# IO1.net
KiCad netlist of a schematic drawn in Altium Designer
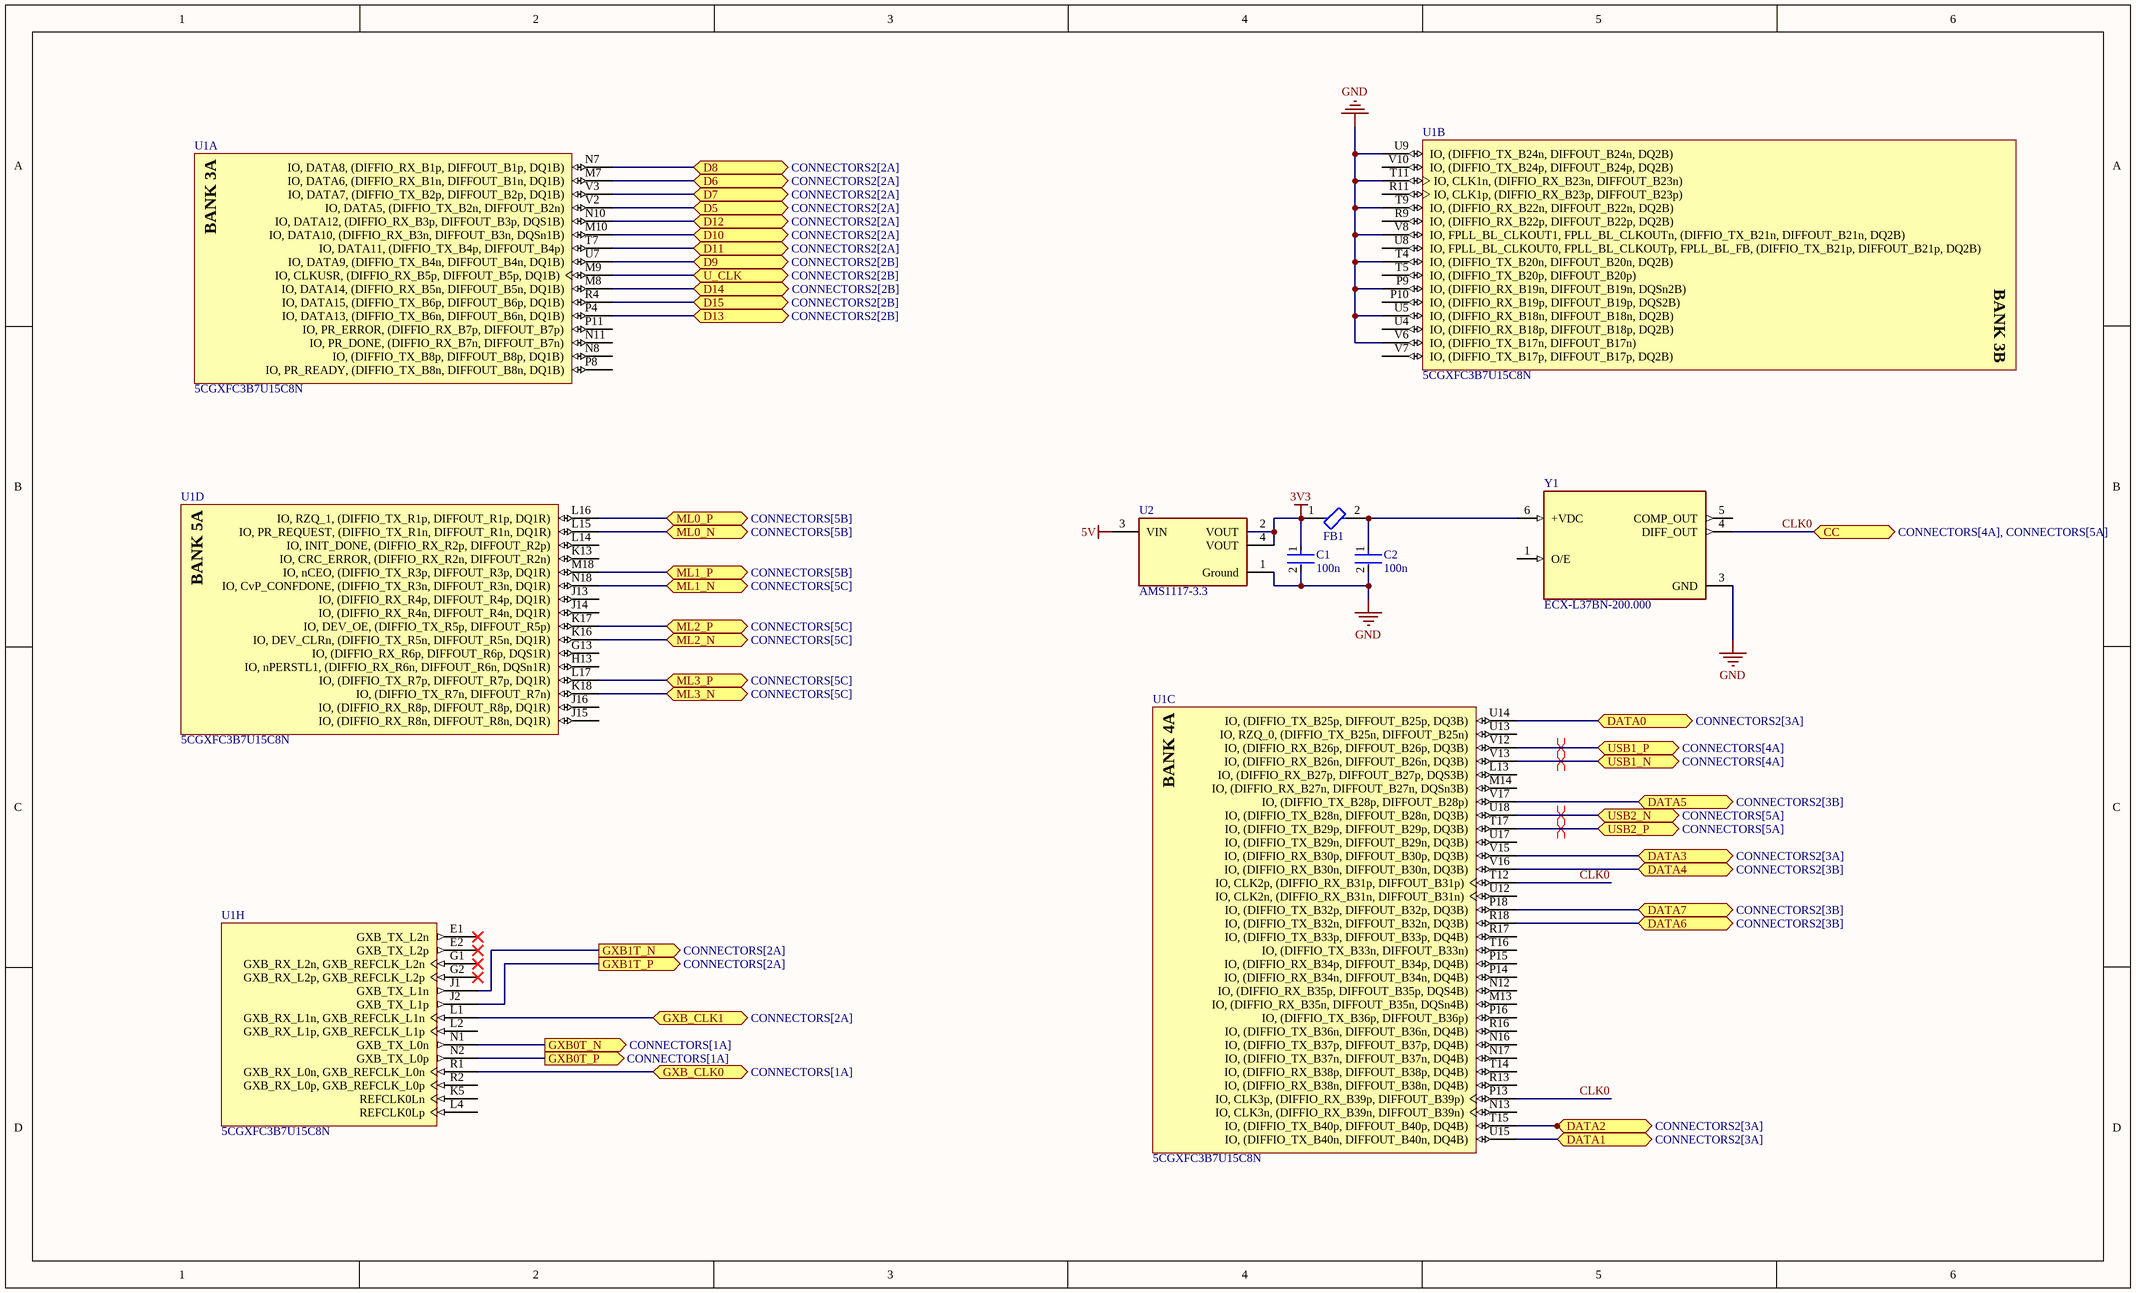
[diagram p0: IO1.SchDoc]

(export (version "E")
  (design (tool "Eeschema 10.0.6"))
  (components
    (comp (ref "C1")
      (value "100n")
      (footprint "FP-CL10-IPC_C")
      (description "Cap Ceramic 4.7uF 10V X5R ±10% Pad SMD 0603 +85°C T/R")
      (fields (field (name "TOLERANCE") "10%"))
      (libsource (lib "Altium Content Vault") (part "b4654b650e69147ec39a6b967a45e02"))
    )
    (comp (ref "C2")
      (value "100n")
      (footprint "FP-CL10-IPC_C")
      (description "Cap Ceramic 4.7uF 10V X5R ±10% Pad SMD 0603 +85°C T/R")
      (fields (field (name "TOLERANCE") "10%"))
      (libsource (lib "Altium Content Vault") (part "b4654b650e69147ec39a6b967a45e02"))
    )
    (comp (ref "FB1")
      (value "BLM18KG121TN1D")
      (footprint "FP-BLM18-0_15-t0_6-d1_2-IPC_A")
      (description "FERRITE BEAD 120 OHM 0603 1LN")
      (fields (field (name "TOLERANCE") "25%"))
      (libsource (lib "Altium Content Vault") (part "5f30dd21d616792df468990f7003faa"))
    )
    (comp (ref "U1")
      (value "5CGXFC3B7U15C8N")
      (footprint "ALTR-UBGA324_A-150")
      (fields (field (name "MANUFACTURER") "Altera"))
      (libsource (lib "") (part "ALTR-5CGXFC3B6U15_1"))
    )
    (comp (ref "U2")
      (value "AMS1117-3.3")
      (footprint "FP-AMS1117-IPC_C")
      (description "LDO Voltage Regulators 1A, 3.3V")
      (fields
        (field (name "OCTOPART") "https://octopart.com/ams1117-3.3-advanced+monolithic+systems-25899300")
        (field (name "MANUFACTURER") "Advanced Monolithic Systems")
      )
      (libsource (lib "Altium Content Vault") (part "8bdbb5f8e77002000e30dd2845d0354"))
    )
    (comp (ref "Y1")
      (value "ECX-L37BN-200.000")
      (footprint "OSC_ECX-L37BN-200.000")
      (description "200 MHz XO (Standard) LVDS Oscillator 3.3V Enable/Disable 6-SMD, No Lead")
      (fields (field (name "MF") "ECS Inc."))
      (libsource (lib "ECX-L37BN-200.000") (part "ECX-L37BN-200.000"))
    )
  )
  (nets
    (net (code "1") (name "/CLK0") (class "Default")
      (node (ref "U1") (pin "P13") (pinfunction "IO,_CLK3p,_(DIFFIO_RX_B39p,_DIFFOUT_B39p)_P13") (pintype "bidirectional"))
      (node (ref "U1") (pin "T12") (pinfunction "IO,_CLK2p,_(DIFFIO_RX_B31p,_DIFFOUT_B31p)_T12") (pintype "bidirectional"))
      (node (ref "Y1") (pin "4") (pinfunction "DIFF_OUT_4") (pintype "output"))
    )
    (net (code "2") (name "/D5") (class "Default")
      (node (ref "U1") (pin "V2") (pinfunction "IO,_DATA5,_(DIFFIO_TX_B2n,_DIFFOUT_B2n)_V2") (pintype "bidirectional"))
    )
    (net (code "3") (name "/D6") (class "Default")
      (node (ref "U1") (pin "M7") (pinfunction "IO,_DATA6,_(DIFFIO_RX_B1n,_DIFFOUT_B1n,_DQ1B)_M7") (pintype "bidirectional"))
    )
    (net (code "4") (name "/D7") (class "Default")
      (node (ref "U1") (pin "V3") (pinfunction "IO,_DATA7,_(DIFFIO_TX_B2p,_DIFFOUT_B2p,_DQ1B)_V3") (pintype "bidirectional"))
    )
    (net (code "5") (name "/D8") (class "Default")
      (node (ref "U1") (pin "N7") (pinfunction "IO,_DATA8,_(DIFFIO_RX_B1p,_DIFFOUT_B1p,_DQ1B)_N7") (pintype "bidirectional"))
    )
    (net (code "6") (name "/D9") (class "Default")
      (node (ref "U1") (pin "U7") (pinfunction "IO,_DATA9,_(DIFFIO_TX_B4n,_DIFFOUT_B4n,_DQ1B)_U7") (pintype "bidirectional"))
    )
    (net (code "7") (name "/D10") (class "Default")
      (node (ref "U1") (pin "M10") (pinfunction "IO,_DATA10,_(DIFFIO_RX_B3n,_DIFFOUT_B3n,_DQSn1B)_M10") (pintype "bidirectional"))
    )
    (net (code "8") (name "/D11") (class "Default")
      (node (ref "U1") (pin "T7") (pinfunction "IO,_DATA11,_(DIFFIO_TX_B4p,_DIFFOUT_B4p)_T7") (pintype "bidirectional"))
    )
    (net (code "9") (name "/D12") (class "Default")
      (node (ref "U1") (pin "N10") (pinfunction "IO,_DATA12,_(DIFFIO_RX_B3p,_DIFFOUT_B3p,_DQS1B)_N10") (pintype "bidirectional"))
    )
    (net (code "10") (name "/D13") (class "Default")
      (node (ref "U1") (pin "P4") (pinfunction "IO,_DATA13,_(DIFFIO_TX_B6n,_DIFFOUT_B6n,_DQ1B)_P4") (pintype "bidirectional"))
    )
    (net (code "11") (name "/D14") (class "Default")
      (node (ref "U1") (pin "M8") (pinfunction "IO,_DATA14,_(DIFFIO_RX_B5n,_DIFFOUT_B5n,_DQ1B)_M8") (pintype "bidirectional"))
    )
    (net (code "12") (name "/D15") (class "Default")
      (node (ref "U1") (pin "R4") (pinfunction "IO,_DATA15,_(DIFFIO_TX_B6p,_DIFFOUT_B6p,_DQ1B)_R4") (pintype "bidirectional"))
    )
    (net (code "13") (name "/DATA0") (class "Default")
      (node (ref "U1") (pin "U14") (pinfunction "IO,_(DIFFIO_TX_B25p,_DIFFOUT_B25p,_DQ3B)_U14") (pintype "bidirectional"))
    )
    (net (code "14") (name "/DATA1") (class "Default")
      (node (ref "U1") (pin "U15") (pinfunction "IO,_(DIFFIO_TX_B40n,_DIFFOUT_B40n,_DQ4B)_U15") (pintype "bidirectional"))
    )
    (net (code "15") (name "/DATA2") (class "Default")
      (node (ref "U1") (pin "T15") (pinfunction "IO,_(DIFFIO_TX_B40p,_DIFFOUT_B40p,_DQ4B)_T15") (pintype "bidirectional"))
    )
    (net (code "16") (name "/DATA3") (class "Default")
      (node (ref "U1") (pin "V15") (pinfunction "IO,_(DIFFIO_RX_B30p,_DIFFOUT_B30p,_DQ3B)_V15") (pintype "bidirectional"))
    )
    (net (code "17") (name "/DATA4") (class "Default")
      (node (ref "U1") (pin "V16") (pinfunction "IO,_(DIFFIO_RX_B30n,_DIFFOUT_B30n,_DQ3B)_V16") (pintype "bidirectional"))
    )
    (net (code "18") (name "/DATA5") (class "Default")
      (node (ref "U1") (pin "V17") (pinfunction "IO,_(DIFFIO_TX_B28p,_DIFFOUT_B28p)_V17") (pintype "bidirectional"))
    )
    (net (code "19") (name "/DATA6") (class "Default")
      (node (ref "U1") (pin "R18") (pinfunction "IO,_(DIFFIO_TX_B32n,_DIFFOUT_B32n,_DQ3B)_R18") (pintype "bidirectional"))
    )
    (net (code "20") (name "/DATA7") (class "Default")
      (node (ref "U1") (pin "P18") (pinfunction "IO,_(DIFFIO_TX_B32p,_DIFFOUT_B32p,_DQ3B)_P18") (pintype "bidirectional"))
    )
    (net (code "21") (name "/GXB0T_N") (class "Default")
      (node (ref "U1") (pin "N1") (pinfunction "GXB_TX_L0n_N1") (pintype "output"))
    )
    (net (code "22") (name "/GXB0T_P") (class "Default")
      (node (ref "U1") (pin "N2") (pinfunction "GXB_TX_L0p_N2") (pintype "output"))
    )
    (net (code "23") (name "/GXB1T_N") (class "Default")
      (node (ref "U1") (pin "J1") (pinfunction "GXB_TX_L1n_J1") (pintype "output"))
    )
    (net (code "24") (name "/GXB1T_P") (class "Default")
      (node (ref "U1") (pin "J2") (pinfunction "GXB_TX_L1p_J2") (pintype "output"))
    )
    (net (code "25") (name "/GXB_CLK0") (class "Default")
      (node (ref "U1") (pin "R1") (pinfunction "GXB_RX_L0n,_GXB_REFCLK_L0n_R1") (pintype "input"))
    )
    (net (code "26") (name "/GXB_CLK1") (class "Default")
      (node (ref "U1") (pin "L1") (pinfunction "GXB_RX_L1n,_GXB_REFCLK_L1n_L1") (pintype "input"))
    )
    (net (code "27") (name "/ML0_N") (class "Default")
      (node (ref "U1") (pin "L15") (pinfunction "IO,_PR_REQUEST,_(DIFFIO_TX_R1n,_DIFFOUT_R1n,_DQ1R)_L15") (pintype "bidirectional"))
    )
    (net (code "28") (name "/ML0_P") (class "Default")
      (node (ref "U1") (pin "L16") (pinfunction "IO,_RZQ_1,_(DIFFIO_TX_R1p,_DIFFOUT_R1p,_DQ1R)_L16") (pintype "bidirectional"))
    )
    (net (code "29") (name "/ML1_N") (class "Default")
      (node (ref "U1") (pin "N18") (pinfunction "IO,_CvP_CONFDONE,_(DIFFIO_TX_R3n,_DIFFOUT_R3n,_DQ1R)_N18") (pintype "bidirectional"))
    )
    (net (code "30") (name "/ML1_P") (class "Default")
      (node (ref "U1") (pin "M18") (pinfunction "IO,_nCEO,_(DIFFIO_TX_R3p,_DIFFOUT_R3p,_DQ1R)_M18") (pintype "bidirectional"))
    )
    (net (code "31") (name "/ML2_N") (class "Default")
      (node (ref "U1") (pin "K16") (pinfunction "IO,_DEV_CLRn,_(DIFFIO_TX_R5n,_DIFFOUT_R5n,_DQ1R)_K16") (pintype "bidirectional"))
    )
    (net (code "32") (name "/ML2_P") (class "Default")
      (node (ref "U1") (pin "K17") (pinfunction "IO,_DEV_OE,_(DIFFIO_TX_R5p,_DIFFOUT_R5p)_K17") (pintype "bidirectional"))
    )
    (net (code "33") (name "/ML3_N") (class "Default")
      (node (ref "U1") (pin "K18") (pinfunction "IO,_(DIFFIO_TX_R7n,_DIFFOUT_R7n)_K18") (pintype "bidirectional"))
    )
    (net (code "34") (name "/ML3_P") (class "Default")
      (node (ref "U1") (pin "L17") (pinfunction "IO,_(DIFFIO_TX_R7p,_DIFFOUT_R7p,_DQ1R)_L17") (pintype "bidirectional"))
    )
    (net (code "35") (name "/USB1_N") (class "Default")
      (node (ref "U1") (pin "V13") (pinfunction "IO,_(DIFFIO_RX_B26n,_DIFFOUT_B26n,_DQ3B)_V13") (pintype "bidirectional"))
    )
    (net (code "36") (name "/USB1_P") (class "Default")
      (node (ref "U1") (pin "V12") (pinfunction "IO,_(DIFFIO_RX_B26p,_DIFFOUT_B26p,_DQ3B)_V12") (pintype "bidirectional"))
    )
    (net (code "37") (name "/USB2_N") (class "Default")
      (node (ref "U1") (pin "U18") (pinfunction "IO,_(DIFFIO_TX_B28n,_DIFFOUT_B28n,_DQ3B)_U18") (pintype "bidirectional"))
    )
    (net (code "38") (name "/USB2_P") (class "Default")
      (node (ref "U1") (pin "T17") (pinfunction "IO,_(DIFFIO_TX_B29p,_DIFFOUT_B29p,_DQ3B)_T17") (pintype "bidirectional"))
    )
    (net (code "39") (name "/U_CLK") (class "Default")
      (node (ref "U1") (pin "M9") (pinfunction "IO,_CLKUSR,_(DIFFIO_RX_B5p,_DIFFOUT_B5p,_DQ1B)_M9") (pintype "bidirectional"))
    )
    (net (code "40") (name "3V3") (class "Default")
      (node (ref "C1") (pin "1") (pinfunction "1_1") (pintype "passive"))
      (node (ref "FB1") (pin "1") (pinfunction "1_1") (pintype "passive"))
      (node (ref "U2") (pin "2") (pinfunction "VOUT_2") (pintype "passive"))
      (node (ref "U2") (pin "4") (pinfunction "VOUT_4") (pintype "passive"))
    )
    (net (code "41") (name "5V") (class "Default")
      (node (ref "U2") (pin "3") (pinfunction "VIN_3") (pintype "power_in"))
    )
    (net (code "42") (name "GND") (class "Default")
      (node (ref "C1") (pin "2") (pinfunction "2_2") (pintype "passive"))
      (node (ref "C2") (pin "2") (pinfunction "2_2") (pintype "passive"))
      (node (ref "U1") (pin "P9") (pinfunction "IO,_(DIFFIO_RX_B19n,_DIFFOUT_B19n,_DQSn2B)_P9") (pintype "bidirectional"))
      (node (ref "U1") (pin "T11") (pinfunction "IO,_CLK1n,_(DIFFIO_RX_B23n,_DIFFOUT_B23n)_T11") (pintype "bidirectional"))
      (node (ref "U1") (pin "T4") (pinfunction "IO,_(DIFFIO_TX_B20n,_DIFFOUT_B20n,_DQ2B)_T4") (pintype "bidirectional"))
      (node (ref "U1") (pin "T9") (pinfunction "IO,_(DIFFIO_RX_B22n,_DIFFOUT_B22n,_DQ2B)_T9") (pintype "bidirectional"))
      (node (ref "U1") (pin "U5") (pinfunction "IO,_(DIFFIO_RX_B18n,_DIFFOUT_B18n,_DQ2B)_U5") (pintype "bidirectional"))
      (node (ref "U1") (pin "U9") (pinfunction "IO,_(DIFFIO_TX_B24n,_DIFFOUT_B24n,_DQ2B)_U9") (pintype "bidirectional"))
      (node (ref "U1") (pin "V6") (pinfunction "IO,_(DIFFIO_TX_B17n,_DIFFOUT_B17n)_V6") (pintype "bidirectional"))
      (node (ref "U1") (pin "V8") (pinfunction "IO,_FPLL_BL_CLKOUT1,_FPLL_BL_CLKOUTn,_(DIFFIO_TX_B21n,_DIFFOUT_B21n,_DQ2B)_V8") (pintype "bidirectional"))
      (node (ref "U2") (pin "1") (pinfunction "Ground_1") (pintype "power_in"))
      (node (ref "Y1") (pin "3") (pinfunction "GND_3") (pintype "power_in"))
    )
    (net (code "43") (name "Net-(Y1-+VDC)") (class "Default")
      (node (ref "C2") (pin "1") (pinfunction "1_1") (pintype "passive"))
      (node (ref "FB1") (pin "2") (pinfunction "2_2") (pintype "passive"))
      (node (ref "Y1") (pin "6") (pinfunction "+VDC_6") (pintype "input"))
    )
    (net (code "44") (name "unconnected-(U1A-IO,_(DIFFIO_TX_B8p,_DIFFOUT_B8p,_DQ1B)-PadN8)") (class "Default")
      (node (ref "U1") (pin "N8") (pinfunction "IO,_(DIFFIO_TX_B8p,_DIFFOUT_B8p,_DQ1B)_N8") (pintype "bidirectional"))
    )
    (net (code "45") (name "unconnected-(U1A-IO,_PR_DONE,_(DIFFIO_RX_B7n,_DIFFOUT_B7n)-PadN11)") (class "Default")
      (node (ref "U1") (pin "N11") (pinfunction "IO,_PR_DONE,_(DIFFIO_RX_B7n,_DIFFOUT_B7n)_N11") (pintype "bidirectional"))
    )
    (net (code "46") (name "unconnected-(U1A-IO,_PR_ERROR,_(DIFFIO_RX_B7p,_DIFFOUT_B7p)-PadP11)") (class "Default")
      (node (ref "U1") (pin "P11") (pinfunction "IO,_PR_ERROR,_(DIFFIO_RX_B7p,_DIFFOUT_B7p)_P11") (pintype "bidirectional"))
    )
    (net (code "47") (name "unconnected-(U1A-IO,_PR_READY,_(DIFFIO_TX_B8n,_DIFFOUT_B8n,_DQ1B)-PadP8)") (class "Default")
      (node (ref "U1") (pin "P8") (pinfunction "IO,_PR_READY,_(DIFFIO_TX_B8n,_DIFFOUT_B8n,_DQ1B)_P8") (pintype "bidirectional"))
    )
    (net (code "48") (name "unconnected-(U1B-IO,_(DIFFIO_RX_B18p,_DIFFOUT_B18p,_DQ2B)-PadU4)") (class "Default")
      (node (ref "U1") (pin "U4") (pinfunction "IO,_(DIFFIO_RX_B18p,_DIFFOUT_B18p,_DQ2B)_U4") (pintype "bidirectional"))
    )
    (net (code "49") (name "unconnected-(U1B-IO,_(DIFFIO_RX_B19p,_DIFFOUT_B19p,_DQS2B)-PadP10)") (class "Default")
      (node (ref "U1") (pin "P10") (pinfunction "IO,_(DIFFIO_RX_B19p,_DIFFOUT_B19p,_DQS2B)_P10") (pintype "bidirectional"))
    )
    (net (code "50") (name "unconnected-(U1B-IO,_(DIFFIO_RX_B22p,_DIFFOUT_B22p,_DQ2B)-PadR9)") (class "Default")
      (node (ref "U1") (pin "R9") (pinfunction "IO,_(DIFFIO_RX_B22p,_DIFFOUT_B22p,_DQ2B)_R9") (pintype "bidirectional"))
    )
    (net (code "51") (name "unconnected-(U1B-IO,_(DIFFIO_TX_B17p,_DIFFOUT_B17p,_DQ2B)-PadV7)") (class "Default")
      (node (ref "U1") (pin "V7") (pinfunction "IO,_(DIFFIO_TX_B17p,_DIFFOUT_B17p,_DQ2B)_V7") (pintype "bidirectional"))
    )
    (net (code "52") (name "unconnected-(U1B-IO,_(DIFFIO_TX_B20p,_DIFFOUT_B20p)-PadT5)") (class "Default")
      (node (ref "U1") (pin "T5") (pinfunction "IO,_(DIFFIO_TX_B20p,_DIFFOUT_B20p)_T5") (pintype "bidirectional"))
    )
    (net (code "53") (name "unconnected-(U1B-IO,_(DIFFIO_TX_B24p,_DIFFOUT_B24p,_DQ2B)-PadV10)") (class "Default")
      (node (ref "U1") (pin "V10") (pinfunction "IO,_(DIFFIO_TX_B24p,_DIFFOUT_B24p,_DQ2B)_V10") (pintype "bidirectional"))
    )
    (net (code "54") (name "unconnected-(U1B-IO,_CLK1p,_(DIFFIO_RX_B23p,_DIFFOUT_B23p)-PadR11)") (class "Default")
      (node (ref "U1") (pin "R11") (pinfunction "IO,_CLK1p,_(DIFFIO_RX_B23p,_DIFFOUT_B23p)_R11") (pintype "bidirectional"))
    )
    (net (code "55") (name "unconnected-(U1B-IO,_FPLL_BL_CLKOUT0,_FPLL_BL_CLKOUTp,_FPLL_BL_FB,_(DIFFIO_TX_B21p,_DIFFOUT_B21p,_DQ2B)-PadU8)") (class "Default")
      (node (ref "U1") (pin "U8") (pinfunction "IO,_FPLL_BL_CLKOUT0,_FPLL_BL_CLKOUTp,_FPLL_BL_FB,_(DIFFIO_TX_B21p,_DIFFOUT_B21p,_DQ2B)_U8") (pintype "bidirectional"))
    )
    (net (code "56") (name "unconnected-(U1C-IO,_(DIFFIO_RX_B27n,_DIFFOUT_B27n,_DQSn3B)-PadM14)") (class "Default")
      (node (ref "U1") (pin "M14") (pinfunction "IO,_(DIFFIO_RX_B27n,_DIFFOUT_B27n,_DQSn3B)_M14") (pintype "bidirectional"))
    )
    (net (code "57") (name "unconnected-(U1C-IO,_(DIFFIO_RX_B27p,_DIFFOUT_B27p,_DQS3B)-PadL13)") (class "Default")
      (node (ref "U1") (pin "L13") (pinfunction "IO,_(DIFFIO_RX_B27p,_DIFFOUT_B27p,_DQS3B)_L13") (pintype "bidirectional"))
    )
    (net (code "58") (name "unconnected-(U1C-IO,_(DIFFIO_RX_B34n,_DIFFOUT_B34n,_DQ4B)-PadP14)") (class "Default")
      (node (ref "U1") (pin "P14") (pinfunction "IO,_(DIFFIO_RX_B34n,_DIFFOUT_B34n,_DQ4B)_P14") (pintype "bidirectional"))
    )
    (net (code "59") (name "unconnected-(U1C-IO,_(DIFFIO_RX_B34p,_DIFFOUT_B34p,_DQ4B)-PadP15)") (class "Default")
      (node (ref "U1") (pin "P15") (pinfunction "IO,_(DIFFIO_RX_B34p,_DIFFOUT_B34p,_DQ4B)_P15") (pintype "bidirectional"))
    )
    (net (code "60") (name "unconnected-(U1C-IO,_(DIFFIO_RX_B35n,_DIFFOUT_B35n,_DQSn4B)-PadM13)") (class "Default")
      (node (ref "U1") (pin "M13") (pinfunction "IO,_(DIFFIO_RX_B35n,_DIFFOUT_B35n,_DQSn4B)_M13") (pintype "bidirectional"))
    )
    (net (code "61") (name "unconnected-(U1C-IO,_(DIFFIO_RX_B35p,_DIFFOUT_B35p,_DQS4B)-PadN12)") (class "Default")
      (node (ref "U1") (pin "N12") (pinfunction "IO,_(DIFFIO_RX_B35p,_DIFFOUT_B35p,_DQS4B)_N12") (pintype "bidirectional"))
    )
    (net (code "62") (name "unconnected-(U1C-IO,_(DIFFIO_RX_B38n,_DIFFOUT_B38n,_DQ4B)-PadR13)") (class "Default")
      (node (ref "U1") (pin "R13") (pinfunction "IO,_(DIFFIO_RX_B38n,_DIFFOUT_B38n,_DQ4B)_R13") (pintype "bidirectional"))
    )
    (net (code "63") (name "unconnected-(U1C-IO,_(DIFFIO_RX_B38p,_DIFFOUT_B38p,_DQ4B)-PadT14)") (class "Default")
      (node (ref "U1") (pin "T14") (pinfunction "IO,_(DIFFIO_RX_B38p,_DIFFOUT_B38p,_DQ4B)_T14") (pintype "bidirectional"))
    )
    (net (code "64") (name "unconnected-(U1C-IO,_(DIFFIO_TX_B29n,_DIFFOUT_B29n,_DQ3B)-PadU17)") (class "Default")
      (node (ref "U1") (pin "U17") (pinfunction "IO,_(DIFFIO_TX_B29n,_DIFFOUT_B29n,_DQ3B)_U17") (pintype "bidirectional"))
    )
    (net (code "65") (name "unconnected-(U1C-IO,_(DIFFIO_TX_B33n,_DIFFOUT_B33n)-PadT16)") (class "Default")
      (node (ref "U1") (pin "T16") (pinfunction "IO,_(DIFFIO_TX_B33n,_DIFFOUT_B33n)_T16") (pintype "bidirectional"))
    )
    (net (code "66") (name "unconnected-(U1C-IO,_(DIFFIO_TX_B33p,_DIFFOUT_B33p,_DQ4B)-PadR17)") (class "Default")
      (node (ref "U1") (pin "R17") (pinfunction "IO,_(DIFFIO_TX_B33p,_DIFFOUT_B33p,_DQ4B)_R17") (pintype "bidirectional"))
    )
    (net (code "67") (name "unconnected-(U1C-IO,_(DIFFIO_TX_B36n,_DIFFOUT_B36n,_DQ4B)-PadR16)") (class "Default")
      (node (ref "U1") (pin "R16") (pinfunction "IO,_(DIFFIO_TX_B36n,_DIFFOUT_B36n,_DQ4B)_R16") (pintype "bidirectional"))
    )
    (net (code "68") (name "unconnected-(U1C-IO,_(DIFFIO_TX_B36p,_DIFFOUT_B36p)-PadP16)") (class "Default")
      (node (ref "U1") (pin "P16") (pinfunction "IO,_(DIFFIO_TX_B36p,_DIFFOUT_B36p)_P16") (pintype "bidirectional"))
    )
    (net (code "69") (name "unconnected-(U1C-IO,_(DIFFIO_TX_B37n,_DIFFOUT_B37n,_DQ4B)-PadN17)") (class "Default")
      (node (ref "U1") (pin "N17") (pinfunction "IO,_(DIFFIO_TX_B37n,_DIFFOUT_B37n,_DQ4B)_N17") (pintype "bidirectional"))
    )
    (net (code "70") (name "unconnected-(U1C-IO,_(DIFFIO_TX_B37p,_DIFFOUT_B37p,_DQ4B)-PadN16)") (class "Default")
      (node (ref "U1") (pin "N16") (pinfunction "IO,_(DIFFIO_TX_B37p,_DIFFOUT_B37p,_DQ4B)_N16") (pintype "bidirectional"))
    )
    (net (code "71") (name "unconnected-(U1C-IO,_CLK2n,_(DIFFIO_RX_B31n,_DIFFOUT_B31n)-PadU12)") (class "Default")
      (node (ref "U1") (pin "U12") (pinfunction "IO,_CLK2n,_(DIFFIO_RX_B31n,_DIFFOUT_B31n)_U12") (pintype "bidirectional"))
    )
    (net (code "72") (name "unconnected-(U1C-IO,_CLK3n,_(DIFFIO_RX_B39n,_DIFFOUT_B39n)-PadN13)") (class "Default")
      (node (ref "U1") (pin "N13") (pinfunction "IO,_CLK3n,_(DIFFIO_RX_B39n,_DIFFOUT_B39n)_N13") (pintype "bidirectional"))
    )
    (net (code "73") (name "unconnected-(U1C-IO,_RZQ_0,_(DIFFIO_TX_B25n,_DIFFOUT_B25n)-PadU13)") (class "Default")
      (node (ref "U1") (pin "U13") (pinfunction "IO,_RZQ_0,_(DIFFIO_TX_B25n,_DIFFOUT_B25n)_U13") (pintype "bidirectional"))
    )
    (net (code "74") (name "unconnected-(U1D-IO,_(DIFFIO_RX_R4n,_DIFFOUT_R4n,_DQ1R)-PadJ14)") (class "Default")
      (node (ref "U1") (pin "J14") (pinfunction "IO,_(DIFFIO_RX_R4n,_DIFFOUT_R4n,_DQ1R)_J14") (pintype "bidirectional"))
    )
    (net (code "75") (name "unconnected-(U1D-IO,_(DIFFIO_RX_R4p,_DIFFOUT_R4p,_DQ1R)-PadJ13)") (class "Default")
      (node (ref "U1") (pin "J13") (pinfunction "IO,_(DIFFIO_RX_R4p,_DIFFOUT_R4p,_DQ1R)_J13") (pintype "bidirectional"))
    )
    (net (code "76") (name "unconnected-(U1D-IO,_(DIFFIO_RX_R6p,_DIFFOUT_R6p,_DQS1R)-PadG13)") (class "Default")
      (node (ref "U1") (pin "G13") (pinfunction "IO,_(DIFFIO_RX_R6p,_DIFFOUT_R6p,_DQS1R)_G13") (pintype "bidirectional"))
    )
    (net (code "77") (name "unconnected-(U1D-IO,_(DIFFIO_RX_R8n,_DIFFOUT_R8n,_DQ1R)-PadJ15)") (class "Default")
      (node (ref "U1") (pin "J15") (pinfunction "IO,_(DIFFIO_RX_R8n,_DIFFOUT_R8n,_DQ1R)_J15") (pintype "bidirectional"))
    )
    (net (code "78") (name "unconnected-(U1D-IO,_(DIFFIO_RX_R8p,_DIFFOUT_R8p,_DQ1R)-PadJ16)") (class "Default")
      (node (ref "U1") (pin "J16") (pinfunction "IO,_(DIFFIO_RX_R8p,_DIFFOUT_R8p,_DQ1R)_J16") (pintype "bidirectional"))
    )
    (net (code "79") (name "unconnected-(U1D-IO,_CRC_ERROR,_(DIFFIO_RX_R2n,_DIFFOUT_R2n)-PadK13)") (class "Default")
      (node (ref "U1") (pin "K13") (pinfunction "IO,_CRC_ERROR,_(DIFFIO_RX_R2n,_DIFFOUT_R2n)_K13") (pintype "bidirectional"))
    )
    (net (code "80") (name "unconnected-(U1D-IO,_INIT_DONE,_(DIFFIO_RX_R2p,_DIFFOUT_R2p)-PadL14)") (class "Default")
      (node (ref "U1") (pin "L14") (pinfunction "IO,_INIT_DONE,_(DIFFIO_RX_R2p,_DIFFOUT_R2p)_L14") (pintype "bidirectional"))
    )
    (net (code "81") (name "unconnected-(U1D-IO,_nPERSTL1,_(DIFFIO_RX_R6n,_DIFFOUT_R6n,_DQSn1R)-PadH13)") (class "Default")
      (node (ref "U1") (pin "H13") (pinfunction "IO,_nPERSTL1,_(DIFFIO_RX_R6n,_DIFFOUT_R6n,_DQSn1R)_H13") (pintype "bidirectional"))
    )
    (net (code "82") (name "unconnected-(U1H-GXB_RX_L0p,_GXB_REFCLK_L0p-PadR2)") (class "Default")
      (node (ref "U1") (pin "R2") (pinfunction "GXB_RX_L0p,_GXB_REFCLK_L0p_R2") (pintype "input"))
    )
    (net (code "83") (name "unconnected-(U1H-GXB_RX_L1p,_GXB_REFCLK_L1p-PadL2)") (class "Default")
      (node (ref "U1") (pin "L2") (pinfunction "GXB_RX_L1p,_GXB_REFCLK_L1p_L2") (pintype "input"))
    )
    (net (code "84") (name "unconnected-(U1H-GXB_RX_L2n,_GXB_REFCLK_L2n-PadG1)") (class "Default")
      (node (ref "U1") (pin "G1") (pinfunction "GXB_RX_L2n,_GXB_REFCLK_L2n_G1") (pintype "input+no_connect"))
    )
    (net (code "85") (name "unconnected-(U1H-GXB_RX_L2p,_GXB_REFCLK_L2p-PadG2)") (class "Default")
      (node (ref "U1") (pin "G2") (pinfunction "GXB_RX_L2p,_GXB_REFCLK_L2p_G2") (pintype "input+no_connect"))
    )
    (net (code "86") (name "unconnected-(U1H-GXB_TX_L2n-PadE1)") (class "Default")
      (node (ref "U1") (pin "E1") (pinfunction "GXB_TX_L2n_E1") (pintype "output+no_connect"))
    )
    (net (code "87") (name "unconnected-(U1H-GXB_TX_L2p-PadE2)") (class "Default")
      (node (ref "U1") (pin "E2") (pinfunction "GXB_TX_L2p_E2") (pintype "output+no_connect"))
    )
    (net (code "88") (name "unconnected-(U1H-REFCLK0Ln-PadK5)") (class "Default")
      (node (ref "U1") (pin "K5") (pinfunction "REFCLK0Ln_K5") (pintype "input"))
    )
    (net (code "89") (name "unconnected-(U1H-REFCLK0Lp-PadL4)") (class "Default")
      (node (ref "U1") (pin "L4") (pinfunction "REFCLK0Lp_L4") (pintype "input"))
    )
    (net (code "90") (name "unconnected-(Y1-COMP_OUT-Pad5)") (class "Default")
      (node (ref "Y1") (pin "5") (pinfunction "COMP_OUT_5") (pintype "output"))
    )
    (net (code "91") (name "unconnected-(Y1-O{slash}E-Pad1)") (class "Default")
      (node (ref "Y1") (pin "1") (pinfunction "O/E_1") (pintype "input"))
    )
  )
)
